# I2S_Audio.net
KiCad netlist of a schematic drawn in Altium Designer
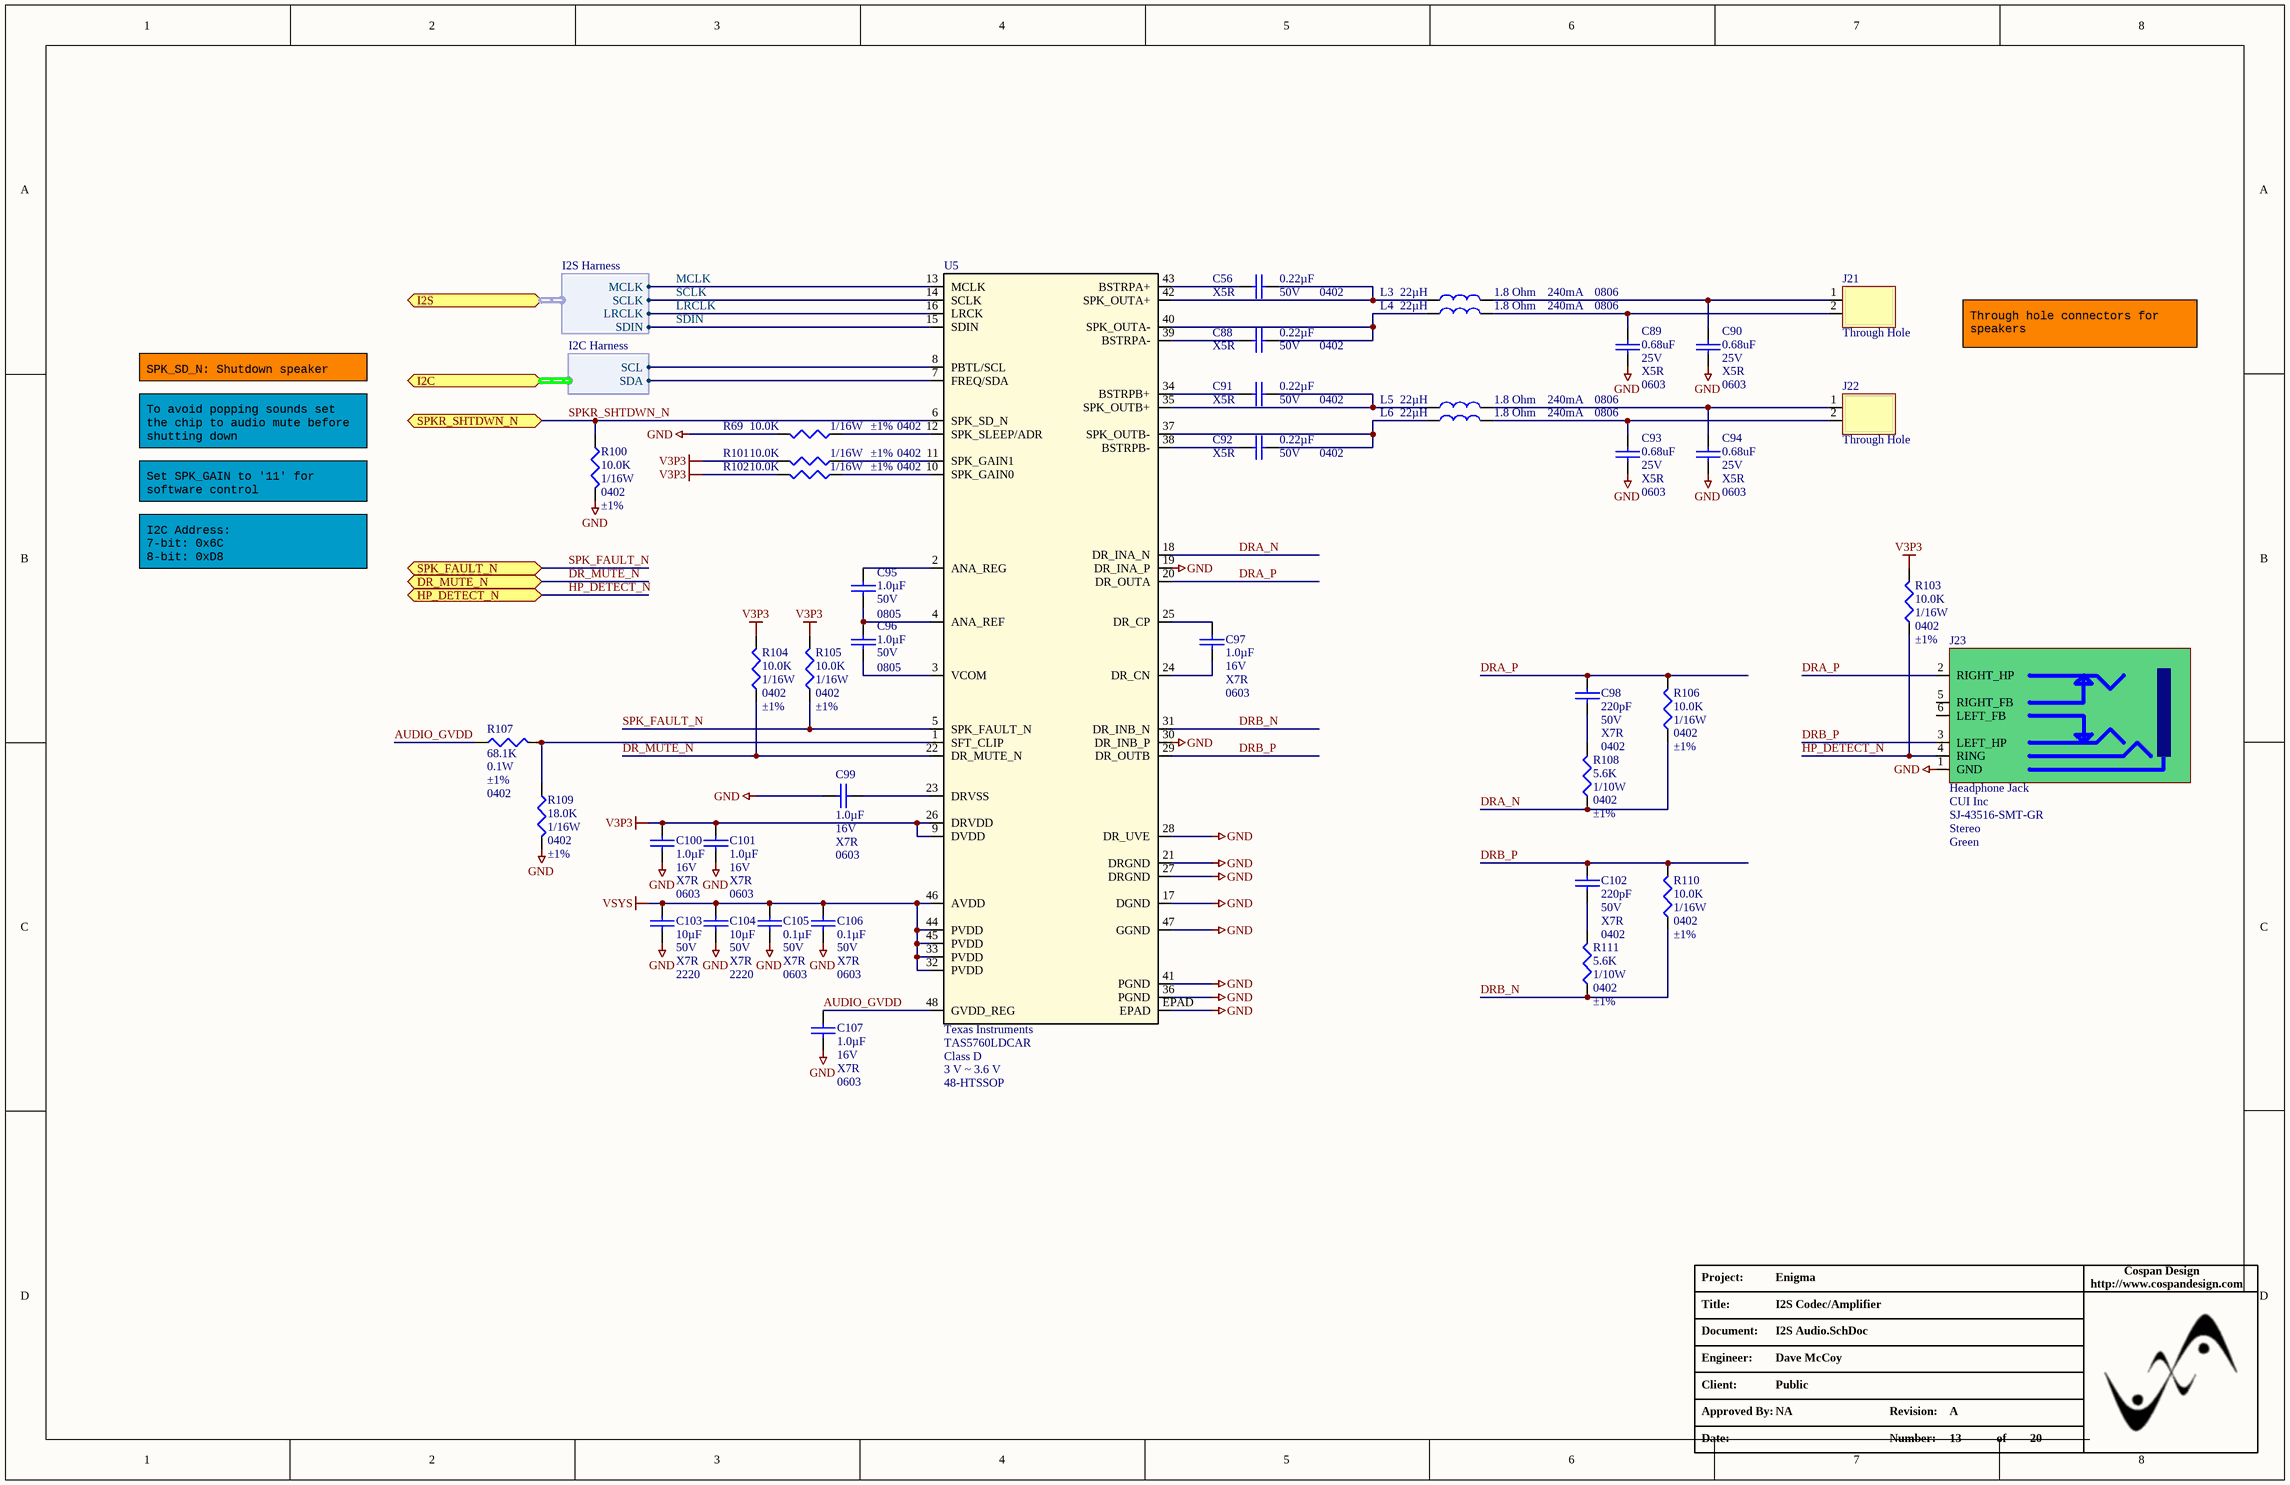
[diagram p0: I2S Audio.SchDoc]

(export (version "E")
  (design (tool "Eeschema 10.0.6"))
  (components
    (comp (ref "C56")
      (value "C_0402_0.22UF_50V")
      (footprint "C_0402")
      (description "CAP CER 0.22UF 50V X5R 0402")
      (fields
        (field (name "MANUFACTURER") "Taiyo Yuden")
        (field (name "MANUFACTURER PART NUMBER") "UMK105BJ224KV-F")
        (field (name "CAPACITANCE") "0.22µF")
        (field (name "VOLTAGE - RATED") "50V")
        (field (name "TEMPERATURE COEFFICIENT") "X5R")
        (field (name "PACKAGE / CASE") "0402")
      )
      (libsource (lib "Main Library") (part "C_0402_0.22UF_50V"))
    )
    (comp (ref "C88")
      (value "C_0402_0.22UF_50V")
      (footprint "C_0402")
      (description "CAP CER 0.22UF 50V X5R 0402")
      (fields
        (field (name "MANUFACTURER") "Taiyo Yuden")
        (field (name "MANUFACTURER PART NUMBER") "UMK105BJ224KV-F")
        (field (name "CAPACITANCE") "0.22µF")
        (field (name "VOLTAGE - RATED") "50V")
        (field (name "TEMPERATURE COEFFICIENT") "X5R")
        (field (name "PACKAGE / CASE") "0402")
      )
      (libsource (lib "Main Library") (part "C_0402_0.22UF_50V"))
    )
    (comp (ref "C89")
      (value "C_0603_0.68uF_25V")
      (footprint "C_ERA-0603")
      (description "CAP CER 0.68UF 25V X5R 0603")
      (fields
        (field (name "MANUFACTURER") "Wurth Electronics Inc.")
        (field (name "MANUFACTURER PART NUMBER") "885012106021")
        (field (name "CAPACITANCE") "0.68uF")
        (field (name "VOLTAGE - RATED") "25V")
        (field (name "TEMPERATURE COEFFICIENT") "X5R")
        (field (name "PACKAGE / CASE") "0603")
      )
      (libsource (lib "Cospan Design") (part "C_0603_0.68uF_25V"))
    )
    (comp (ref "C90")
      (value "C_0603_0.68uF_25V")
      (footprint "C_ERA-0603")
      (description "CAP CER 0.68UF 25V X5R 0603")
      (fields
        (field (name "MANUFACTURER") "Wurth Electronics Inc.")
        (field (name "MANUFACTURER PART NUMBER") "885012106021")
        (field (name "CAPACITANCE") "0.68uF")
        (field (name "VOLTAGE - RATED") "25V")
        (field (name "TEMPERATURE COEFFICIENT") "X5R")
        (field (name "PACKAGE / CASE") "0603")
      )
      (libsource (lib "Cospan Design") (part "C_0603_0.68uF_25V"))
    )
    (comp (ref "C91")
      (value "C_0402_0.22UF_50V")
      (footprint "C_0402")
      (description "CAP CER 0.22UF 50V X5R 0402")
      (fields
        (field (name "MANUFACTURER") "Taiyo Yuden")
        (field (name "MANUFACTURER PART NUMBER") "UMK105BJ224KV-F")
        (field (name "CAPACITANCE") "0.22µF")
        (field (name "VOLTAGE - RATED") "50V")
        (field (name "TEMPERATURE COEFFICIENT") "X5R")
        (field (name "PACKAGE / CASE") "0402")
      )
      (libsource (lib "Main Library") (part "C_0402_0.22UF_50V"))
    )
    (comp (ref "C92")
      (value "C_0402_0.22UF_50V")
      (footprint "C_0402")
      (description "CAP CER 0.22UF 50V X5R 0402")
      (fields
        (field (name "MANUFACTURER") "Taiyo Yuden")
        (field (name "MANUFACTURER PART NUMBER") "UMK105BJ224KV-F")
        (field (name "CAPACITANCE") "0.22µF")
        (field (name "VOLTAGE - RATED") "50V")
        (field (name "TEMPERATURE COEFFICIENT") "X5R")
        (field (name "PACKAGE / CASE") "0402")
      )
      (libsource (lib "Main Library") (part "C_0402_0.22UF_50V"))
    )
    (comp (ref "C93")
      (value "C_0603_0.68uF_25V")
      (footprint "C_ERA-0603")
      (description "CAP CER 0.68UF 25V X5R 0603")
      (fields
        (field (name "MANUFACTURER") "Wurth Electronics Inc.")
        (field (name "MANUFACTURER PART NUMBER") "885012106021")
        (field (name "CAPACITANCE") "0.68uF")
        (field (name "VOLTAGE - RATED") "25V")
        (field (name "TEMPERATURE COEFFICIENT") "X5R")
        (field (name "PACKAGE / CASE") "0603")
      )
      (libsource (lib "Cospan Design") (part "C_0603_0.68uF_25V"))
    )
    (comp (ref "C94")
      (value "C_0603_0.68uF_25V")
      (footprint "C_ERA-0603")
      (description "CAP CER 0.68UF 25V X5R 0603")
      (fields
        (field (name "MANUFACTURER") "Wurth Electronics Inc.")
        (field (name "MANUFACTURER PART NUMBER") "885012106021")
        (field (name "CAPACITANCE") "0.68uF")
        (field (name "VOLTAGE - RATED") "25V")
        (field (name "TEMPERATURE COEFFICIENT") "X5R")
        (field (name "PACKAGE / CASE") "0603")
      )
      (libsource (lib "Cospan Design") (part "C_0603_0.68uF_25V"))
    )
    (comp (ref "C95")
      (value "1.0uF")
      (footprint "C_ERA-0805")
      (description "CAP CER 1UF 50V X7R 0805")
      (fields
        (field (name "MANUFACTURER") "Murata Electronics North America")
        (field (name "MANUFACTURER PART NUMBER") "GRM21BR71H105KA12L")
        (field (name "CAPACITANCE") "1.0µF")
        (field (name "VOLTAGE - RATED") "50V")
        (field (name "PACKAGE / CASE") "0805")
      )
      (libsource (lib "Main Library") (part "C_0805_1.0uF_50V"))
    )
    (comp (ref "C96")
      (value "1.0uF")
      (footprint "C_ERA-0805")
      (description "CAP CER 1UF 50V X7R 0805")
      (fields
        (field (name "MANUFACTURER") "Murata Electronics North America")
        (field (name "MANUFACTURER PART NUMBER") "GRM21BR71H105KA12L")
        (field (name "CAPACITANCE") "1.0µF")
        (field (name "VOLTAGE - RATED") "50V")
        (field (name "PACKAGE / CASE") "0805")
      )
      (libsource (lib "Main Library") (part "C_0805_1.0uF_50V"))
    )
    (comp (ref "C97")
      (value "1.0uF")
      (footprint "C_ERA-0603")
      (description "CAP CER 1UF 16V 10% X7R 0603")
      (fields
        (field (name "MANUFACTURER") "Yageo")
        (field (name "MANUFACTURER PART NUMBER") "CC0603KRX7R7BB105")
        (field (name "CAPACITANCE") "1.0µF")
        (field (name "VOLTAGE - RATED") "16V")
        (field (name "TEMPERATURE COEFFICIENT") "X7R")
        (field (name "PACKAGE / CASE") "0603")
      )
      (libsource (lib "Main LibraryX") (part "C_0603_1.0uF_16V"))
    )
    (comp (ref "C98")
      (value "220pF")
      (footprint "C_0402")
      (description "CAP CER 220PF 50V 10% X7R 0402")
      (fields
        (field (name "MANUFACTURER") "Murata Electronics North America")
        (field (name "MANUFACTURER PART NUMBER") "GRM155R71H221KA01D")
        (field (name "CAPACITANCE") "220pF")
        (field (name "VOLTAGE - RATED") "50V")
        (field (name "TEMPERATURE COEFFICIENT") "X7R")
        (field (name "PACKAGE / CASE") "0402")
      )
      (libsource (lib "Main Library") (part "C_0402_220PF_50V"))
    )
    (comp (ref "C99")
      (value "1.0uF")
      (footprint "C_ERA-0603")
      (description "CAP CER 1UF 16V 10% X7R 0603")
      (fields
        (field (name "MANUFACTURER") "Yageo")
        (field (name "MANUFACTURER PART NUMBER") "CC0603KRX7R7BB105")
        (field (name "CAPACITANCE") "1.0µF")
        (field (name "VOLTAGE - RATED") "16V")
        (field (name "TEMPERATURE COEFFICIENT") "X7R")
        (field (name "PACKAGE / CASE") "0603")
      )
      (libsource (lib "Main LibraryX") (part "C_0603_1.0uF_16V"))
    )
    (comp (ref "C100")
      (value "1.0uF")
      (footprint "C_ERA-0603")
      (description "CAP CER 1UF 16V 10% X7R 0603")
      (fields
        (field (name "MANUFACTURER") "Yageo")
        (field (name "MANUFACTURER PART NUMBER") "CC0603KRX7R7BB105")
        (field (name "CAPACITANCE") "1.0µF")
        (field (name "VOLTAGE - RATED") "16V")
        (field (name "TEMPERATURE COEFFICIENT") "X7R")
        (field (name "PACKAGE / CASE") "0603")
      )
      (libsource (lib "Main LibraryX") (part "C_0603_1.0uF_16V"))
    )
    (comp (ref "C101")
      (value "1.0uF")
      (footprint "C_ERA-0603")
      (description "CAP CER 1UF 16V 10% X7R 0603")
      (fields
        (field (name "MANUFACTURER") "Yageo")
        (field (name "MANUFACTURER PART NUMBER") "CC0603KRX7R7BB105")
        (field (name "CAPACITANCE") "1.0µF")
        (field (name "VOLTAGE - RATED") "16V")
        (field (name "TEMPERATURE COEFFICIENT") "X7R")
        (field (name "PACKAGE / CASE") "0603")
      )
      (libsource (lib "Main LibraryX") (part "C_0603_1.0uF_16V"))
    )
    (comp (ref "C102")
      (value "220pF")
      (footprint "C_0402")
      (description "CAP CER 220PF 50V 10% X7R 0402")
      (fields
        (field (name "MANUFACTURER") "Murata Electronics North America")
        (field (name "MANUFACTURER PART NUMBER") "GRM155R71H221KA01D")
        (field (name "CAPACITANCE") "220pF")
        (field (name "VOLTAGE - RATED") "50V")
        (field (name "TEMPERATURE COEFFICIENT") "X7R")
        (field (name "PACKAGE / CASE") "0402")
      )
      (libsource (lib "Main Library") (part "C_0402_220PF_50V"))
    )
    (comp (ref "C103")
      (value "10µF")
      (footprint "C_ERA-2220")
      (description "CAP CER 10UF 50V X7R 20% 2220")
      (fields
        (field (name "MANUFACTURER") "TDK Corporation")
        (field (name "MANUFACTURER PART NUMBER") "C5750X7R1H106K230KB")
        (field (name "CAPACITANCE") "10µF")
        (field (name "VOLTAGE - RATED") "50V")
        (field (name "TEMPERATURE COEFFICIENT") "X7R")
        (field (name "PACKAGE / CASE") "2220")
      )
      (libsource (lib "Main LibraryX") (part "C_2220_10UF_50V"))
    )
    (comp (ref "C104")
      (value "10µF")
      (footprint "C_ERA-2220")
      (description "CAP CER 10UF 50V X7R 20% 2220")
      (fields
        (field (name "MANUFACTURER") "TDK Corporation")
        (field (name "MANUFACTURER PART NUMBER") "C5750X7R1H106K230KB")
        (field (name "CAPACITANCE") "10µF")
        (field (name "VOLTAGE - RATED") "50V")
        (field (name "TEMPERATURE COEFFICIENT") "X7R")
        (field (name "PACKAGE / CASE") "2220")
      )
      (libsource (lib "Main LibraryX") (part "C_2220_10UF_50V"))
    )
    (comp (ref "C105")
      (value "C_0603_0.1µF")
      (footprint "C_ERA-0603")
      (description "CAP CER 0.1UF 50V X7R 0603")
      (fields
        (field (name "MANUFACTURER") "Samsung Electro-Mechanics America, Inc.")
        (field (name "MANUFACTURER PART NUMBER") "CL10B104KB8SFNC")
        (field (name "CAPACITANCE") "0.1µF")
        (field (name "VOLTAGE - RATED") "50V")
        (field (name "TEMPERATURE COEFFICIENT") "X7R")
        (field (name "PACKAGE / CASE") "0603")
      )
      (libsource (lib "Cospan Design") (part "C_0603_0.1µF"))
    )
    (comp (ref "C106")
      (value "C_0603_0.1µF")
      (footprint "C_ERA-0603")
      (description "CAP CER 0.1UF 50V X7R 0603")
      (fields
        (field (name "MANUFACTURER") "Samsung Electro-Mechanics America, Inc.")
        (field (name "MANUFACTURER PART NUMBER") "CL10B104KB8SFNC")
        (field (name "CAPACITANCE") "0.1µF")
        (field (name "VOLTAGE - RATED") "50V")
        (field (name "TEMPERATURE COEFFICIENT") "X7R")
        (field (name "PACKAGE / CASE") "0603")
      )
      (libsource (lib "Cospan Design") (part "C_0603_0.1µF"))
    )
    (comp (ref "C107")
      (value "1.0uF")
      (footprint "C_ERA-0603")
      (description "CAP CER 1UF 16V 10% X7R 0603")
      (fields
        (field (name "MANUFACTURER") "Yageo")
        (field (name "MANUFACTURER PART NUMBER") "CC0603KRX7R7BB105")
        (field (name "CAPACITANCE") "1.0µF")
        (field (name "VOLTAGE - RATED") "16V")
        (field (name "TEMPERATURE COEFFICIENT") "X7R")
        (field (name "PACKAGE / CASE") "0603")
      )
      (libsource (lib "Main LibraryX") (part "C_0603_1.0uF_16V"))
    )
    (comp (ref "J21")
      (value "J_HDR1X2_JUMPER")
      (footprint "HDR_1X2")
      (description "CONN HEADER .100\" 2POS TIN PCB")
      (fields
        (field (name "MANUFACTURER") "Samtec")
        (field (name "MANUFACTURER PART NUMBER") "TSW-102-07-T-S")
        (field (name "MOUNTING TYPE") "Through Hole")
      )
      (libsource (lib "Main Library") (part "J_HDR1X2_JUMPER"))
    )
    (comp (ref "J22")
      (value "J_HDR1X2_JUMPER")
      (footprint "HDR_1X2")
      (description "CONN HEADER .100\" 2POS TIN PCB")
      (fields
        (field (name "MANUFACTURER") "Samtec")
        (field (name "MANUFACTURER PART NUMBER") "TSW-102-07-T-S")
        (field (name "MOUNTING TYPE") "Through Hole")
      )
      (libsource (lib "Main Library") (part "J_HDR1X2_JUMPER"))
    )
    (comp (ref "J23")
      (value "Headphone Jack")
      (footprint "HEADPHONE_JACK")
      (description "CONN AUDIO JACK 3.5MM 4COND SMD")
      (fields
        (field (name "MANUFACTURER") "CUI Inc")
        (field (name "MANUFACTURER PART NUMBER") "SJ-43516-SMT-GR")
        (field (name "SIGNAL LINES") "Stereo")
        (field (name "COLOR") "Green")
      )
      (libsource (lib "Main Library") (part "J_HEADPHONE_JACK"))
    )
    (comp (ref "L3")
      (value "CBC2016T220K")
      (footprint "L_0806")
      (description "INDUCTOR 22UH 10% 0806 SMD")
      (fields
        (field (name "MANUFACTURER") "Taiyo Yuden")
        (field (name "TOLERANCE") "±10%")
        (field (name "CURRENT") "240mA")
        (field (name "PACKAGE / CASE") "0806")
        (field (name "INDUCTANCE") "22µH")
        (field (name "DC RESISTANCE (DCR)") "1.8 Ohm")
      )
      (libsource (lib "Main Library") (part "L_0806_22uH"))
    )
    (comp (ref "L4")
      (value "CBC2016T220K")
      (footprint "L_0806")
      (description "INDUCTOR 22UH 10% 0806 SMD")
      (fields
        (field (name "MANUFACTURER") "Taiyo Yuden")
        (field (name "TOLERANCE") "±10%")
        (field (name "CURRENT") "240mA")
        (field (name "PACKAGE / CASE") "0806")
        (field (name "INDUCTANCE") "22µH")
        (field (name "DC RESISTANCE (DCR)") "1.8 Ohm")
      )
      (libsource (lib "Main Library") (part "L_0806_22uH"))
    )
    (comp (ref "L5")
      (value "CBC2016T220K")
      (footprint "L_0806")
      (description "INDUCTOR 22UH 10% 0806 SMD")
      (fields
        (field (name "MANUFACTURER") "Taiyo Yuden")
        (field (name "TOLERANCE") "±10%")
        (field (name "CURRENT") "240mA")
        (field (name "PACKAGE / CASE") "0806")
        (field (name "INDUCTANCE") "22µH")
        (field (name "DC RESISTANCE (DCR)") "1.8 Ohm")
      )
      (libsource (lib "Main Library") (part "L_0806_22uH"))
    )
    (comp (ref "L6")
      (value "CBC2016T220K")
      (footprint "L_0806")
      (description "INDUCTOR 22UH 10% 0806 SMD")
      (fields
        (field (name "MANUFACTURER") "Taiyo Yuden")
        (field (name "TOLERANCE") "±10%")
        (field (name "CURRENT") "240mA")
        (field (name "PACKAGE / CASE") "0806")
        (field (name "INDUCTANCE") "22µH")
        (field (name "DC RESISTANCE (DCR)") "1.8 Ohm")
      )
      (libsource (lib "Main Library") (part "L_0806_22uH"))
    )
    (comp (ref "R69")
      (value "R_0402_10.0K")
      (footprint "R_0402")
      (description "RES 10.0K OHM 1/16W 1% 0402 SMD")
      (fields
        (field (name "MANUFACTURER") "Stackpole Electronics Inc")
        (field (name "MANUFACTURER PART NUMBER") "RMCF0402FT10K0")
        (field (name "RESISTANCE IN OHMS") "10.0K")
        (field (name "POWER (WATTS)") "1/16W")
        (field (name "CASE") "0402")
        (field (name "TOLERANCE") "±1%")
      )
      (libsource (lib "Main Library") (part "R_0402_10.0K"))
    )
    (comp (ref "R100")
      (value "R_0402_10.0K")
      (footprint "R_0402")
      (description "RES 10.0K OHM 1/16W 1% 0402 SMD")
      (fields
        (field (name "MANUFACTURER") "Stackpole Electronics Inc")
        (field (name "MANUFACTURER PART NUMBER") "RMCF0402FT10K0")
        (field (name "RESISTANCE IN OHMS") "10.0K")
        (field (name "POWER (WATTS)") "1/16W")
        (field (name "CASE") "0402")
        (field (name "TOLERANCE") "±1%")
      )
      (libsource (lib "Main Library") (part "R_0402_10.0K"))
    )
    (comp (ref "R101")
      (value "R_0402_10.0K")
      (footprint "R_0402")
      (description "RES 10.0K OHM 1/16W 1% 0402 SMD")
      (fields
        (field (name "MANUFACTURER") "Stackpole Electronics Inc")
        (field (name "MANUFACTURER PART NUMBER") "RMCF0402FT10K0")
        (field (name "RESISTANCE IN OHMS") "10.0K")
        (field (name "POWER (WATTS)") "1/16W")
        (field (name "CASE") "0402")
        (field (name "TOLERANCE") "±1%")
      )
      (libsource (lib "Main Library") (part "R_0402_10.0K"))
    )
    (comp (ref "R102")
      (value "R_0402_10.0K")
      (footprint "R_0402")
      (description "RES 10.0K OHM 1/16W 1% 0402 SMD")
      (fields
        (field (name "MANUFACTURER") "Stackpole Electronics Inc")
        (field (name "MANUFACTURER PART NUMBER") "RMCF0402FT10K0")
        (field (name "RESISTANCE IN OHMS") "10.0K")
        (field (name "POWER (WATTS)") "1/16W")
        (field (name "CASE") "0402")
        (field (name "TOLERANCE") "±1%")
      )
      (libsource (lib "Main Library") (part "R_0402_10.0K"))
    )
    (comp (ref "R103")
      (value "R_0402_10.0K")
      (footprint "R_0402")
      (description "RES 10.0K OHM 1/16W 1% 0402 SMD")
      (fields
        (field (name "MANUFACTURER") "Stackpole Electronics Inc")
        (field (name "MANUFACTURER PART NUMBER") "RMCF0402FT10K0")
        (field (name "RESISTANCE IN OHMS") "10.0K")
        (field (name "POWER (WATTS)") "1/16W")
        (field (name "CASE") "0402")
        (field (name "TOLERANCE") "±1%")
      )
      (libsource (lib "Main Library") (part "R_0402_10.0K"))
    )
    (comp (ref "R104")
      (value "R_0402_10.0K")
      (footprint "R_0402")
      (description "RES 10.0K OHM 1/16W 1% 0402 SMD")
      (fields
        (field (name "MANUFACTURER") "Stackpole Electronics Inc")
        (field (name "MANUFACTURER PART NUMBER") "RMCF0402FT10K0")
        (field (name "RESISTANCE IN OHMS") "10.0K")
        (field (name "POWER (WATTS)") "1/16W")
        (field (name "CASE") "0402")
        (field (name "TOLERANCE") "±1%")
      )
      (libsource (lib "Main Library") (part "R_0402_10.0K"))
    )
    (comp (ref "R105")
      (value "R_0402_10.0K")
      (footprint "R_0402")
      (description "RES 10.0K OHM 1/16W 1% 0402 SMD")
      (fields
        (field (name "MANUFACTURER") "Stackpole Electronics Inc")
        (field (name "MANUFACTURER PART NUMBER") "RMCF0402FT10K0")
        (field (name "RESISTANCE IN OHMS") "10.0K")
        (field (name "POWER (WATTS)") "1/16W")
        (field (name "CASE") "0402")
        (field (name "TOLERANCE") "±1%")
      )
      (libsource (lib "Main Library") (part "R_0402_10.0K"))
    )
    (comp (ref "R106")
      (value "R_0402_10.0K")
      (footprint "R_0402")
      (description "RES 10.0K OHM 1/16W 1% 0402 SMD")
      (fields
        (field (name "MANUFACTURER") "Stackpole Electronics Inc")
        (field (name "MANUFACTURER PART NUMBER") "RMCF0402FT10K0")
        (field (name "RESISTANCE IN OHMS") "10.0K")
        (field (name "POWER (WATTS)") "1/16W")
        (field (name "CASE") "0402")
        (field (name "TOLERANCE") "±1%")
      )
      (libsource (lib "Main Library") (part "R_0402_10.0K"))
    )
    (comp (ref "R107")
      (value "R_0402_68.1K")
      (footprint "R_0402")
      (description "RES 68.1K OHM 1/10W 1% 0402 SMD")
      (fields
        (field (name "MANUFACTURER") "Panasonic - ECG")
        (field (name "MANUFACTURER PART NUMBER") "ERJ-2RKF6812X")
        (field (name "RESISTANCE IN OHMS") "68.1K")
        (field (name "POWER (WATTS)") "0.1W")
        (field (name "TOLERANCE") "±1%")
        (field (name "CASE") "0402")
      )
      (libsource (lib "Main Library") (part "R_0402_68.1K"))
    )
    (comp (ref "R108")
      (value "5.6k Ohms")
      (footprint "R_0402")
      (description "RES 5.60K OHM 1/10W 1% 0402 SMD")
      (fields
        (field (name "MANUFACTURER") "Yageo")
        (field (name "MANUFACTURER PART NUMBER") "RC0402FR-075K6L")
        (field (name "RESISTANCE IN OHMS") "5.6K")
        (field (name "POWER (WATTS)") "1/10W")
        (field (name "CASE") "0402")
        (field (name "TOLERANCE") "±1%")
      )
      (libsource (lib "Main LibraryX") (part "R_0402_5.6K"))
    )
    (comp (ref "R109")
      (value "18.0k Ohms")
      (footprint "R_0402")
      (description "RES SMD 18K OHM 1% 1/16W 0402")
      (fields
        (field (name "MANUFACTURER") "Yageo")
        (field (name "MANUFACTURER PART NUMBER") "RC0402FR-0718KL")
        (field (name "RESISTANCE IN OHMS") "18.0K")
        (field (name "POWER (WATTS)") "1/16W")
        (field (name "CASE") "0402")
        (field (name "TOLERANCE") "±1%")
      )
      (libsource (lib "Cospan Design") (part "R_0402_18.0K"))
    )
    (comp (ref "R110")
      (value "R_0402_10.0K")
      (footprint "R_0402")
      (description "RES 10.0K OHM 1/16W 1% 0402 SMD")
      (fields
        (field (name "MANUFACTURER") "Stackpole Electronics Inc")
        (field (name "MANUFACTURER PART NUMBER") "RMCF0402FT10K0")
        (field (name "RESISTANCE IN OHMS") "10.0K")
        (field (name "POWER (WATTS)") "1/16W")
        (field (name "CASE") "0402")
        (field (name "TOLERANCE") "±1%")
      )
      (libsource (lib "Main Library") (part "R_0402_10.0K"))
    )
    (comp (ref "R111")
      (value "5.6k Ohms")
      (footprint "R_0402")
      (description "RES 5.60K OHM 1/10W 1% 0402 SMD")
      (fields
        (field (name "MANUFACTURER") "Yageo")
        (field (name "MANUFACTURER PART NUMBER") "RC0402FR-075K6L")
        (field (name "RESISTANCE IN OHMS") "5.6K")
        (field (name "POWER (WATTS)") "1/10W")
        (field (name "CASE") "0402")
        (field (name "TOLERANCE") "±1%")
      )
      (libsource (lib "Main LibraryX") (part "R_0402_5.6K"))
    )
    (comp (ref "U5")
      (value "U_TAS5760LDCAR")
      (footprint "DCA48_6P4X3P6")
      (description "IC AUDIO AMP DGTL D 48HTSSOP")
      (fields
        (field (name "MANUFACTURER") "Texas Instruments")
        (field (name "MANUFACTURER PART NUMBER") "TAS5760LDCAR")
        (field (name "TYPE") "Class D")
        (field (name "VOLTAGE - SUPPLY") "3 V ~ 3.6 V")
        (field (name "SUPPLIER DEVICE PACKAGE") "48-HTSSOP")
      )
      (libsource (lib "Cospan Design") (part "U_TAS5760LDCAR"))
    )
  )
  (nets
    (net (code "4") (name "/AUDIO_GVDD") (class "Default")
      (node (ref "C107") (pin "2") (pinfunction "2_2") (pintype "passive"))
      (node (ref "R107") (pin "1") (pinfunction "1_1") (pintype "passive"))
      (node (ref "U5") (pin "48") (pinfunction "GVDD_REG_48") (pintype "passive"))
    )
    (net (code "5") (name "/DRA_N") (class "Default")
      (node (ref "R106") (pin "2") (pinfunction "2_2") (pintype "passive"))
      (node (ref "R108") (pin "2") (pinfunction "2_2") (pintype "passive"))
      (node (ref "U5") (pin "18") (pinfunction "DR_INA_N_18") (pintype "passive"))
    )
    (net (code "6") (name "/DRA_P") (class "Default")
      (node (ref "C98") (pin "2") (pinfunction "2_2") (pintype "passive"))
      (node (ref "J23") (pin "2") (pinfunction "RIGHT_HP_2") (pintype "passive"))
      (node (ref "R106") (pin "1") (pinfunction "1_1") (pintype "passive"))
      (node (ref "U5") (pin "20") (pinfunction "DR_OUTA_20") (pintype "passive"))
    )
    (net (code "7") (name "/DRB_N") (class "Default")
      (node (ref "R110") (pin "2") (pinfunction "2_2") (pintype "passive"))
      (node (ref "R111") (pin "2") (pinfunction "2_2") (pintype "passive"))
      (node (ref "U5") (pin "31") (pinfunction "DR_INB_N_31") (pintype "passive"))
    )
    (net (code "8") (name "/DRB_P") (class "Default")
      (node (ref "C102") (pin "2") (pinfunction "2_2") (pintype "passive"))
      (node (ref "J23") (pin "3") (pinfunction "LEFT_HP_3") (pintype "passive"))
      (node (ref "R110") (pin "1") (pinfunction "1_1") (pintype "passive"))
      (node (ref "U5") (pin "29") (pinfunction "DR_OUTB_29") (pintype "passive"))
    )
    (net (code "9") (name "/DR_MUTE_N") (class "Default")
      (node (ref "R104") (pin "1") (pinfunction "1_1") (pintype "passive"))
      (node (ref "U5") (pin "22") (pinfunction "DR_MUTE_N_22") (pintype "passive"))
    )
    (net (code "10") (name "/HP_DETECT_N") (class "Default")
      (node (ref "J23") (pin "4") (pinfunction "RING_4") (pintype "passive"))
      (node (ref "R103") (pin "2") (pinfunction "2_2") (pintype "passive"))
    )
    (net (code "11") (name "/LRCLK") (class "Default")
      (node (ref "U5") (pin "16") (pinfunction "LRCK_16") (pintype "passive"))
    )
    (net (code "12") (name "/MCLK") (class "Default")
      (node (ref "U5") (pin "13") (pinfunction "MCLK_13") (pintype "passive"))
    )
    (net (code "13") (name "/SCL") (class "Default")
      (node (ref "U5") (pin "8") (pinfunction "PBTL/SCL_8") (pintype "passive"))
    )
    (net (code "14") (name "/SCLK") (class "Default")
      (node (ref "U5") (pin "14") (pinfunction "SCLK_14") (pintype "passive"))
    )
    (net (code "15") (name "/SDA") (class "Default")
      (node (ref "U5") (pin "7") (pinfunction "FREQ/SDA_7") (pintype "passive"))
    )
    (net (code "16") (name "/SDIN") (class "Default")
      (node (ref "U5") (pin "15") (pinfunction "SDIN_15") (pintype "passive"))
    )
    (net (code "17") (name "/SPKR_SHTDWN_N") (class "Default")
      (node (ref "R100") (pin "2") (pinfunction "2_2") (pintype "passive"))
      (node (ref "U5") (pin "6") (pinfunction "SPK_SD_N_6") (pintype "passive"))
    )
    (net (code "18") (name "/SPK_FAULT_N") (class "Default")
      (node (ref "R105") (pin "1") (pinfunction "1_1") (pintype "passive"))
      (node (ref "U5") (pin "5") (pinfunction "SPK_FAULT_N_5") (pintype "passive"))
    )
    (net (code "21") (name "GND") (class "Default")
      (node (ref "C100") (pin "1") (pinfunction "1_1") (pintype "passive"))
      (node (ref "C101") (pin "1") (pinfunction "1_1") (pintype "passive"))
      (node (ref "C103") (pin "1") (pinfunction "1_1") (pintype "passive"))
      (node (ref "C104") (pin "1") (pinfunction "1_1") (pintype "passive"))
      (node (ref "C105") (pin "1") (pinfunction "1_1") (pintype "passive"))
      (node (ref "C106") (pin "1") (pinfunction "1_1") (pintype "passive"))
      (node (ref "C107") (pin "1") (pinfunction "1_1") (pintype "passive"))
      (node (ref "C89") (pin "1") (pinfunction "1_1") (pintype "passive"))
      (node (ref "C90") (pin "1") (pinfunction "1_1") (pintype "passive"))
      (node (ref "C93") (pin "1") (pinfunction "1_1") (pintype "passive"))
      (node (ref "C94") (pin "1") (pinfunction "1_1") (pintype "passive"))
      (node (ref "C99") (pin "1") (pinfunction "1_1") (pintype "passive"))
      (node (ref "J23") (pin "1") (pinfunction "GND_1") (pintype "passive"))
      (node (ref "R100") (pin "1") (pinfunction "1_1") (pintype "passive"))
      (node (ref "R109") (pin "2") (pinfunction "2_2") (pintype "passive"))
      (node (ref "R69") (pin "1") (pinfunction "1_1") (pintype "passive"))
      (node (ref "U5") (pin "17") (pinfunction "DGND_17") (pintype "passive"))
      (node (ref "U5") (pin "19") (pinfunction "DR_INA_P_19") (pintype "passive"))
      (node (ref "U5") (pin "21") (pinfunction "DRGND_21") (pintype "passive"))
      (node (ref "U5") (pin "27") (pinfunction "DRGND_27") (pintype "passive"))
      (node (ref "U5") (pin "28") (pinfunction "DR_UVE_28") (pintype "passive"))
      (node (ref "U5") (pin "30") (pinfunction "DR_INB_P_30") (pintype "passive"))
      (node (ref "U5") (pin "36") (pinfunction "PGND_36") (pintype "passive"))
      (node (ref "U5") (pin "41") (pinfunction "PGND_41") (pintype "passive"))
      (node (ref "U5") (pin "47") (pinfunction "GGND_47") (pintype "passive"))
      (node (ref "U5") (pin "EPAD") (pinfunction "EPAD_EPAD") (pintype "passive"))
    )
    (net (code "22") (name "Net-(C89-Pad2)") (class "Default")
      (node (ref "C89") (pin "2") (pinfunction "2_2") (pintype "passive"))
      (node (ref "J21") (pin "2") (pinfunction "2_2") (pintype "passive"))
      (node (ref "L4") (pin "2") (pintype "passive"))
    )
    (net (code "23") (name "Net-(C90-Pad2)") (class "Default")
      (node (ref "C90") (pin "2") (pinfunction "2_2") (pintype "passive"))
      (node (ref "J21") (pin "1") (pinfunction "1_1") (pintype "passive"))
      (node (ref "L3") (pin "2") (pintype "passive"))
    )
    (net (code "24") (name "Net-(C93-Pad2)") (class "Default")
      (node (ref "C93") (pin "2") (pinfunction "2_2") (pintype "passive"))
      (node (ref "J22") (pin "2") (pinfunction "2_2") (pintype "passive"))
      (node (ref "L6") (pin "2") (pintype "passive"))
    )
    (net (code "25") (name "Net-(C94-Pad2)") (class "Default")
      (node (ref "C94") (pin "2") (pinfunction "2_2") (pintype "passive"))
      (node (ref "J22") (pin "1") (pinfunction "1_1") (pintype "passive"))
      (node (ref "L5") (pin "2") (pintype "passive"))
    )
    (net (code "26") (name "Net-(C98-Pad1)") (class "Default")
      (node (ref "C98") (pin "1") (pinfunction "1_1") (pintype "passive"))
      (node (ref "R108") (pin "1") (pinfunction "1_1") (pintype "passive"))
    )
    (net (code "27") (name "Net-(C102-Pad1)") (class "Default")
      (node (ref "C102") (pin "1") (pinfunction "1_1") (pintype "passive"))
      (node (ref "R111") (pin "1") (pinfunction "1_1") (pintype "passive"))
    )
    (net (code "28") (name "Net-(U5-ANA_REF)") (class "Default")
      (node (ref "C95") (pin "1") (pinfunction "1_1") (pintype "passive"))
      (node (ref "C96") (pin "2") (pinfunction "2_2") (pintype "passive"))
      (node (ref "U5") (pin "4") (pinfunction "ANA_REF_4") (pintype "passive"))
    )
    (net (code "29") (name "Net-(U5-ANA_REG)") (class "Default")
      (node (ref "C95") (pin "2") (pinfunction "2_2") (pintype "passive"))
      (node (ref "U5") (pin "2") (pinfunction "ANA_REG_2") (pintype "passive"))
    )
    (net (code "30") (name "Net-(U5-BSTRPA+)") (class "Default")
      (node (ref "C56") (pin "2") (pinfunction "2_2") (pintype "passive"))
      (node (ref "U5") (pin "43") (pinfunction "BSTRPA+_43") (pintype "passive"))
    )
    (net (code "31") (name "Net-(U5-BSTRPA-)") (class "Default")
      (node (ref "C88") (pin "2") (pinfunction "2_2") (pintype "passive"))
      (node (ref "U5") (pin "39") (pinfunction "BSTRPA-_39") (pintype "passive"))
    )
    (net (code "32") (name "Net-(U5-BSTRPB+)") (class "Default")
      (node (ref "C91") (pin "2") (pinfunction "2_2") (pintype "passive"))
      (node (ref "U5") (pin "34") (pinfunction "BSTRPB+_34") (pintype "passive"))
    )
    (net (code "33") (name "Net-(U5-BSTRPB-)") (class "Default")
      (node (ref "C92") (pin "2") (pinfunction "2_2") (pintype "passive"))
      (node (ref "U5") (pin "38") (pinfunction "BSTRPB-_38") (pintype "passive"))
    )
    (net (code "34") (name "Net-(U5-DRVSS)") (class "Default")
      (node (ref "C99") (pin "2") (pinfunction "2_2") (pintype "passive"))
      (node (ref "U5") (pin "23") (pinfunction "DRVSS_23") (pintype "passive"))
    )
    (net (code "35") (name "Net-(U5-DR_CN)") (class "Default")
      (node (ref "C97") (pin "1") (pinfunction "1_1") (pintype "passive"))
      (node (ref "U5") (pin "24") (pinfunction "DR_CN_24") (pintype "passive"))
    )
    (net (code "36") (name "Net-(U5-DR_CP)") (class "Default")
      (node (ref "C97") (pin "2") (pinfunction "2_2") (pintype "passive"))
      (node (ref "U5") (pin "25") (pinfunction "DR_CP_25") (pintype "passive"))
    )
    (net (code "37") (name "Net-(U5-SFT_CLIP)") (class "Default")
      (node (ref "R107") (pin "2") (pinfunction "2_2") (pintype "passive"))
      (node (ref "R109") (pin "1") (pinfunction "1_1") (pintype "passive"))
      (node (ref "U5") (pin "1") (pinfunction "SFT_CLIP_1") (pintype "passive"))
    )
    (net (code "38") (name "Net-(U5-SPK_GAIN0)") (class "Default")
      (node (ref "R102") (pin "2") (pinfunction "2_2") (pintype "passive"))
      (node (ref "U5") (pin "10") (pinfunction "SPK_GAIN0_10") (pintype "passive"))
    )
    (net (code "39") (name "Net-(U5-SPK_GAIN1)") (class "Default")
      (node (ref "R101") (pin "2") (pinfunction "2_2") (pintype "passive"))
      (node (ref "U5") (pin "11") (pinfunction "SPK_GAIN1_11") (pintype "passive"))
    )
    (net (code "40") (name "Net-(U5-SPK_OUTA+)") (class "Default")
      (node (ref "C56") (pin "1") (pinfunction "1_1") (pintype "passive"))
      (node (ref "L3") (pin "1") (pintype "passive"))
      (node (ref "U5") (pin "42") (pinfunction "SPK_OUTA+_42") (pintype "passive"))
    )
    (net (code "41") (name "Net-(U5-SPK_OUTA-)") (class "Default")
      (node (ref "C88") (pin "1") (pinfunction "1_1") (pintype "passive"))
      (node (ref "L4") (pin "1") (pintype "passive"))
      (node (ref "U5") (pin "40") (pinfunction "SPK_OUTA-_40") (pintype "passive"))
    )
    (net (code "42") (name "Net-(U5-SPK_OUTB+)") (class "Default")
      (node (ref "C91") (pin "1") (pinfunction "1_1") (pintype "passive"))
      (node (ref "L5") (pin "1") (pintype "passive"))
      (node (ref "U5") (pin "35") (pinfunction "SPK_OUTB+_35") (pintype "passive"))
    )
    (net (code "43") (name "Net-(U5-SPK_OUTB-)") (class "Default")
      (node (ref "C92") (pin "1") (pinfunction "1_1") (pintype "passive"))
      (node (ref "L6") (pin "1") (pintype "passive"))
      (node (ref "U5") (pin "37") (pinfunction "SPK_OUTB-_37") (pintype "passive"))
    )
    (net (code "44") (name "Net-(U5-SPK_SLEEP{slash}ADR)") (class "Default")
      (node (ref "R69") (pin "2") (pinfunction "2_2") (pintype "passive"))
      (node (ref "U5") (pin "12") (pinfunction "SPK_SLEEP/ADR_12") (pintype "passive"))
    )
    (net (code "45") (name "Net-(U5-VCOM)") (class "Default")
      (node (ref "C96") (pin "1") (pinfunction "1_1") (pintype "passive"))
      (node (ref "U5") (pin "3") (pinfunction "VCOM_3") (pintype "passive"))
    )
    (net (code "46") (name "V3P3") (class "Default")
      (node (ref "C100") (pin "2") (pinfunction "2_2") (pintype "passive"))
      (node (ref "C101") (pin "2") (pinfunction "2_2") (pintype "passive"))
      (node (ref "R101") (pin "1") (pinfunction "1_1") (pintype "passive"))
      (node (ref "R102") (pin "1") (pinfunction "1_1") (pintype "passive"))
      (node (ref "R103") (pin "1") (pinfunction "1_1") (pintype "passive"))
      (node (ref "R104") (pin "2") (pinfunction "2_2") (pintype "passive"))
      (node (ref "R105") (pin "2") (pinfunction "2_2") (pintype "passive"))
      (node (ref "U5") (pin "26") (pinfunction "DRVDD_26") (pintype "passive"))
      (node (ref "U5") (pin "9") (pinfunction "DVDD_9") (pintype "passive"))
    )
    (net (code "47") (name "VSYS") (class "Default")
      (node (ref "C103") (pin "2") (pinfunction "2_2") (pintype "passive"))
      (node (ref "C104") (pin "2") (pinfunction "2_2") (pintype "passive"))
      (node (ref "C105") (pin "2") (pinfunction "2_2") (pintype "passive"))
      (node (ref "C106") (pin "2") (pinfunction "2_2") (pintype "passive"))
      (node (ref "U5") (pin "32") (pinfunction "PVDD_32") (pintype "passive"))
      (node (ref "U5") (pin "33") (pinfunction "PVDD_33") (pintype "passive"))
      (node (ref "U5") (pin "44") (pinfunction "PVDD_44") (pintype "passive"))
      (node (ref "U5") (pin "45") (pinfunction "PVDD_45") (pintype "passive"))
      (node (ref "U5") (pin "46") (pinfunction "AVDD_46") (pintype "passive"))
    )
    (net (code "48") (name "unconnected-(J23-LEFT_FB-Pad6)") (class "Default")
      (node (ref "J23") (pin "6") (pinfunction "LEFT_FB_6") (pintype "passive"))
    )
    (net (code "49") (name "unconnected-(J23-RIGHT_FB-Pad5)") (class "Default")
      (node (ref "J23") (pin "5") (pinfunction "RIGHT_FB_5") (pintype "passive"))
    )
  )
)
